# power_SCH1.net
KiCad netlist of a schematic drawn in Altium Designer
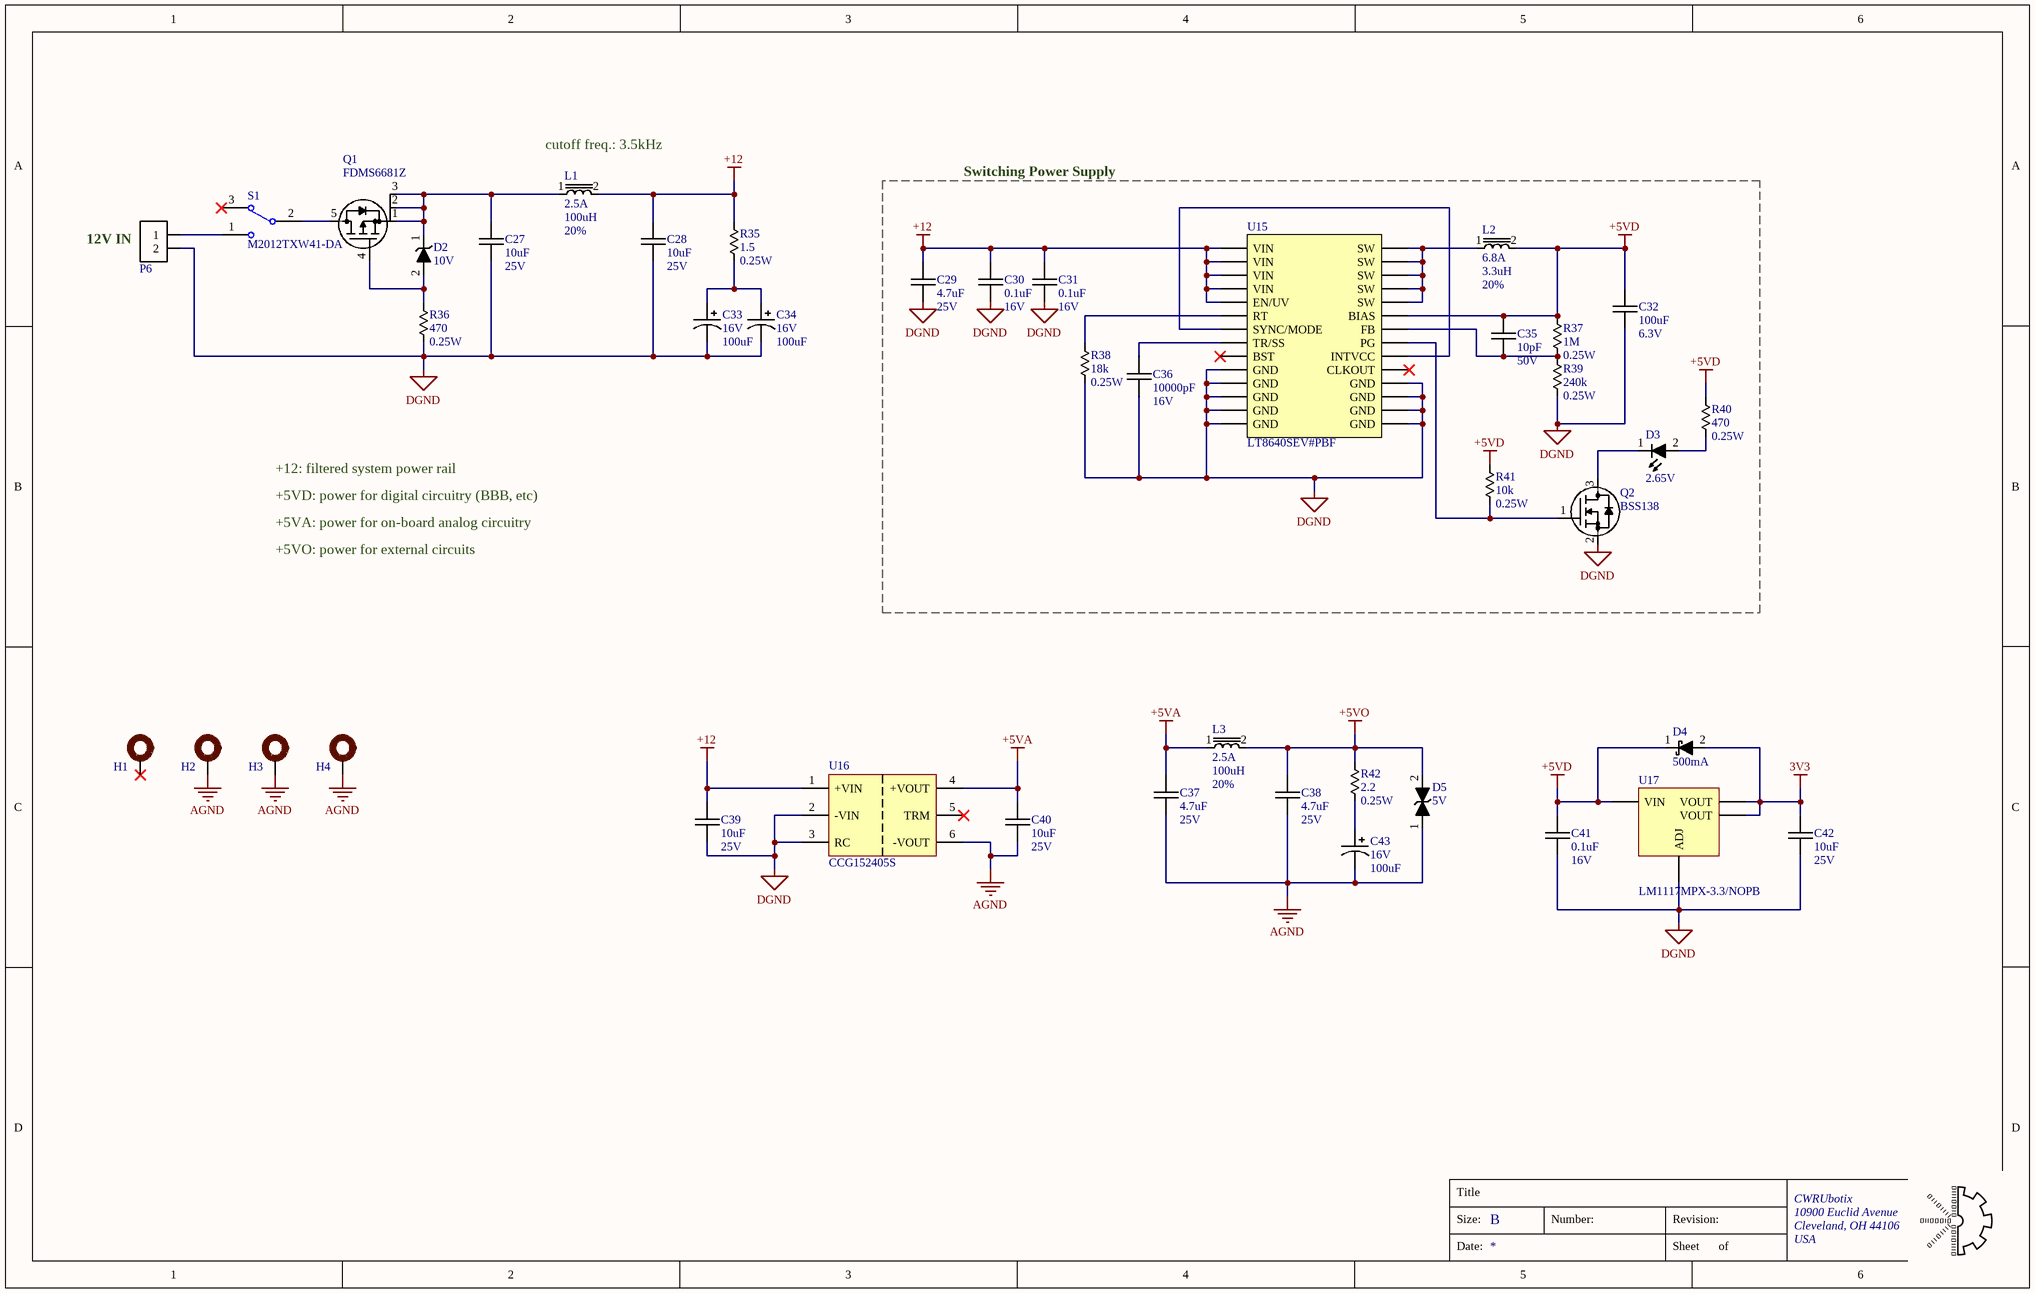
[diagram p0: power_SCH1.SchDoc]

(export (version "E")
  (design (tool "Eeschema 10.0.6"))
  (components
    (comp (ref "C27")
      (value "cap_single_np")
      (footprint "chip_1206")
      (description "CAP, 10uF, ±10%, 25V, X7R, 1206")
      (fields
        (field (name "TOLERANCE") "±10%")
        (field (name "CAPACITANCE") "10uF")
        (field (name "VOLTAGE RATING") "25V")
        (field (name "PART NUMBER") "CAP-00539")
      )
      (libsource (lib "Capacitors") (part "cap_single_np"))
    )
    (comp (ref "C28")
      (value "cap_single_np")
      (footprint "chip_1206")
      (description "CAP, 10uF, ±10%, 25V, X7R, 1206")
      (fields
        (field (name "TOLERANCE") "±10%")
        (field (name "CAPACITANCE") "10uF")
        (field (name "VOLTAGE RATING") "25V")
        (field (name "PART NUMBER") "CAP-00539")
      )
      (libsource (lib "Capacitors") (part "cap_single_np"))
    )
    (comp (ref "C29")
      (value "cap_single_np")
      (footprint "chip_0805")
      (description "CAP, 4.7uF, 10%, 25V, X7R, 0805")
      (fields
        (field (name "TOLERANCE") "10%")
        (field (name "CAPACITANCE") "4.7uF")
        (field (name "VOLTAGE RATING") "25V")
        (field (name "PART NUMBER") "CAP-00128")
      )
      (libsource (lib "Capacitors") (part "cap_single_np"))
    )
    (comp (ref "C30")
      (value "cap_single_np")
      (footprint "chip_0603")
      (description "CAP, 0.1uF, ±10%, 16V, X7R, 0603")
      (fields
        (field (name "TOLERANCE") "±10%")
        (field (name "CAPACITANCE") "0.1uF")
        (field (name "VOLTAGE RATING") "16V")
        (field (name "PART NUMBER") "CAP-00542")
      )
      (libsource (lib "Capacitors") (part "cap_single_np"))
    )
    (comp (ref "C31")
      (value "cap_single_np")
      (footprint "chip_0603")
      (description "CAP, 0.1uF, ±10%, 16V, X7R, 0603")
      (fields
        (field (name "TOLERANCE") "±10%")
        (field (name "CAPACITANCE") "0.1uF")
        (field (name "VOLTAGE RATING") "16V")
        (field (name "PART NUMBER") "CAP-00542")
      )
      (libsource (lib "Capacitors") (part "cap_single_np"))
    )
    (comp (ref "C32")
      (value "cap_single_np")
      (footprint "chip_1206")
      (description "CAP, 100uF, ±20%, 6.3V, X5R, 1206")
      (fields
        (field (name "TOLERANCE") "±20%")
        (field (name "CAPACITANCE") "100uF")
        (field (name "VOLTAGE RATING") "6.3V")
        (field (name "PART NUMBER") "CAP-00551")
      )
      (libsource (lib "Capacitors") (part "cap_single_np"))
    )
    (comp (ref "C33")
      (value "cap_single_p")
      (footprint "chip_2917_AVX_TAJD")
      (description "CAP, 100uF, ±10%, 16V, Tantalum, 2917")
      (fields
        (field (name "TOLERANCE") "±10%")
        (field (name "VOLTAGE RATING") "16V")
        (field (name "CAPACITANCE") "100uF")
        (field (name "PART NUMBER") "CAP-00550")
      )
      (libsource (lib "Capacitors") (part "cap_single_p"))
    )
    (comp (ref "C34")
      (value "cap_single_p")
      (footprint "chip_2917_AVX_TAJD")
      (description "CAP, 100uF, ±10%, 16V, Tantalum, 2917")
      (fields
        (field (name "TOLERANCE") "±10%")
        (field (name "VOLTAGE RATING") "16V")
        (field (name "CAPACITANCE") "100uF")
        (field (name "PART NUMBER") "CAP-00550")
      )
      (libsource (lib "Capacitors") (part "cap_single_p"))
    )
    (comp (ref "C35")
      (value "cap_single_np")
      (footprint "chip_0603")
      (description "CAP, 10pF, ±2%, 50V, C0G, 0603")
      (fields
        (field (name "TOLERANCE") "±2%")
        (field (name "CAPACITANCE") "10pF")
        (field (name "VOLTAGE RATING") "50V")
        (field (name "PART NUMBER") "CAP-00471")
      )
      (libsource (lib "Capacitors") (part "cap_single_np"))
    )
    (comp (ref "C36")
      (value "cap_single_np")
      (footprint "chip_0603")
      (description "CAP, 10000pF, ±10%, 16V, X7R, 0603")
      (fields
        (field (name "TOLERANCE") "±10%")
        (field (name "CAPACITANCE") "10000pF")
        (field (name "VOLTAGE RATING") "16V")
        (field (name "PART NUMBER") "CAP-00543")
      )
      (libsource (lib "Capacitors") (part "cap_single_np"))
    )
    (comp (ref "C37")
      (value "cap_single_np")
      (footprint "chip_0805")
      (description "CAP, 4.7uF, 10%, 25V, X7R, 0805")
      (fields
        (field (name "TOLERANCE") "10%")
        (field (name "CAPACITANCE") "4.7uF")
        (field (name "VOLTAGE RATING") "25V")
        (field (name "PART NUMBER") "CAP-00128")
      )
      (libsource (lib "Capacitors") (part "cap_single_np"))
    )
    (comp (ref "C38")
      (value "cap_single_np")
      (footprint "chip_0805")
      (description "CAP, 4.7uF, 10%, 25V, X7R, 0805")
      (fields
        (field (name "TOLERANCE") "10%")
        (field (name "CAPACITANCE") "4.7uF")
        (field (name "VOLTAGE RATING") "25V")
        (field (name "PART NUMBER") "CAP-00128")
      )
      (libsource (lib "Capacitors") (part "cap_single_np"))
    )
    (comp (ref "C39")
      (value "cap_single_np")
      (footprint "chip_1206")
      (description "CAP, 10uF, ±10%, 25V, X7R, 1206")
      (fields
        (field (name "TOLERANCE") "±10%")
        (field (name "CAPACITANCE") "10uF")
        (field (name "VOLTAGE RATING") "25V")
        (field (name "PART NUMBER") "CAP-00539")
      )
      (libsource (lib "Capacitors") (part "cap_single_np"))
    )
    (comp (ref "C40")
      (value "cap_single_np")
      (footprint "chip_1206")
      (description "CAP, 10uF, ±10%, 25V, X7R, 1206")
      (fields
        (field (name "TOLERANCE") "±10%")
        (field (name "CAPACITANCE") "10uF")
        (field (name "VOLTAGE RATING") "25V")
        (field (name "PART NUMBER") "CAP-00539")
      )
      (libsource (lib "Capacitors") (part "cap_single_np"))
    )
    (comp (ref "C41")
      (value "cap_single_np")
      (footprint "chip_0603")
      (description "CAP, 0.1uF, ±10%, 16V, X7R, 0603")
      (fields
        (field (name "TOLERANCE") "±10%")
        (field (name "CAPACITANCE") "0.1uF")
        (field (name "VOLTAGE RATING") "16V")
        (field (name "PART NUMBER") "CAP-00542")
      )
      (libsource (lib "Capacitors") (part "cap_single_np"))
    )
    (comp (ref "C42")
      (value "cap_single_np")
      (footprint "chip_1206")
      (description "CAP, 10uF, ±10%, 25V, X7R, 1206")
      (fields
        (field (name "TOLERANCE") "±10%")
        (field (name "CAPACITANCE") "10uF")
        (field (name "VOLTAGE RATING") "25V")
        (field (name "PART NUMBER") "CAP-00539")
      )
      (libsource (lib "Capacitors") (part "cap_single_np"))
    )
    (comp (ref "C43")
      (value "cap_single_p")
      (footprint "chip_2917_AVX_TAJD")
      (description "CAP, 100uF, ±10%, 16V, Tantalum, 2917")
      (fields
        (field (name "TOLERANCE") "±10%")
        (field (name "VOLTAGE RATING") "16V")
        (field (name "CAPACITANCE") "100uF")
        (field (name "PART NUMBER") "CAP-00550")
      )
      (libsource (lib "Capacitors") (part "cap_single_p"))
    )
    (comp (ref "D2")
      (value "diode_1")
      (footprint "sod323_0")
      (description "Dio Zen, 10V, 2%, 200mW, SOD-323")
      (fields
        (field (name "REVERSE BREAKDOWN VOLTAGE") "10V")
        (field (name "PART NUMBER") "DIO-00019")
        (field (name "TOLERANCE") "2%")
      )
      (libsource (lib "Diodes") (part "diode_1"))
    )
    (comp (ref "D3")
      (value "diode_4")
      (footprint "chip_0603")
      (description "LED, Blue, 0603, Low current, HELI2 Series")
      (fields
        (field (name "FORWARD VOLTAGE") "2.65V")
        (field (name "PART NUMBER") "DIO-00049")
        (field (name "MANUFACTURER") "Kingbright")
      )
      (libsource (lib "Diodes") (part "diode_4"))
    )
    (comp (ref "D4")
      (value "diode_2")
      (footprint "sod323_0")
      (description "Dio Shtky, 500mA, 0.62V, 30V, SOD-323")
      (fields
        (field (name "CURRENT RATING") "500mA")
        (field (name "PART NUMBER") "DIO-00000")
        (field (name "MANUFACTURER") "ON Semi")
      )
      (libsource (lib "Diodes") (part "diode_2"))
    )
    (comp (ref "D5")
      (value "diode_5")
      (footprint "do-214ac")
      (description "TVS, 5V, 400W")
      (fields
        (field (name "REVERSE BREAKDOWN VOLTAGE") "5V")
        (field (name "PART NUMBER") "DIO-00036")
        (field (name "MANUFACTURER") "ST")
      )
      (libsource (lib "Diodes") (part "diode_5"))
    )
    (comp (ref "H1")
      (value "mounting_hole_0")
      (footprint "#8-32_SOCKET_HEAD")
      (description "#8-32 Mounting Hole for Socket Head Cap Screw")
      (fields (field (name "PART NUMBER") "MISC-00027"))
      (libsource (lib "Misc") (part "mounting_hole_0"))
    )
    (comp (ref "H2")
      (value "mounting_hole_0")
      (footprint "#8-32_SOCKET_HEAD")
      (description "#8-32 Mounting Hole for Socket Head Cap Screw")
      (fields (field (name "PART NUMBER") "MISC-00027"))
      (libsource (lib "Misc") (part "mounting_hole_0"))
    )
    (comp (ref "H3")
      (value "mounting_hole_0")
      (footprint "#8-32_SOCKET_HEAD")
      (description "#8-32 Mounting Hole for Socket Head Cap Screw")
      (fields (field (name "PART NUMBER") "MISC-00027"))
      (libsource (lib "Misc") (part "mounting_hole_0"))
    )
    (comp (ref "H4")
      (value "mounting_hole_0")
      (footprint "#8-32_SOCKET_HEAD")
      (description "#8-32 Mounting Hole for Socket Head Cap Screw")
      (fields (field (name "PART NUMBER") "MISC-00027"))
      (libsource (lib "Misc") (part "mounting_hole_0"))
    )
    (comp (ref "L1")
      (value "ind_1")
      (footprint "WURTH_7447709101")
      (description "Ind, 100uH, 20%, 2.5A, 0.11 Ohm")
      (fields
        (field (name "CURRENT RATING") "2.5A")
        (field (name "INDUCTANCE") "100uH")
        (field (name "TOLERANCE") "20%")
        (field (name "PART NUMBER") "MAG-00102")
        (field (name "MANUFACTURER") "Wurth")
      )
      (libsource (lib "Magnetics") (part "ind_1"))
    )
    (comp (ref "L2")
      (value "ind_1")
      (footprint "TDK_SPM6530")
      (description "Ind, 3.3uH, 20%, 6.8A, EP5")
      (fields
        (field (name "CURRENT RATING") "6.8A")
        (field (name "INDUCTANCE") "3.3uH")
        (field (name "TOLERANCE") "20%")
        (field (name "PART NUMBER") "MAG-00093")
        (field (name "MANUFACTURER") "TDK")
      )
      (libsource (lib "Magnetics") (part "ind_1"))
    )
    (comp (ref "L3")
      (value "ind_1")
      (footprint "WURTH_7447709101")
      (description "Ind, 100uH, 20%, 2.5A, 0.11 Ohm")
      (fields
        (field (name "CURRENT RATING") "2.5A")
        (field (name "INDUCTANCE") "100uH")
        (field (name "TOLERANCE") "20%")
        (field (name "PART NUMBER") "MAG-00102")
        (field (name "MANUFACTURER") "Wurth")
      )
      (libsource (lib "Magnetics") (part "ind_1"))
    )
    (comp (ref "P6")
      (value "conn-2x1_0")
      (footprint "TERM_3.50MM_2x1_0")
      (description "Term Blk, 2 Pos, 16A, 3.5mm Pitch")
      (fields (field (name "PART NUMBER") "CONN-00023") (field (name "MANUFACTURER") "Phoenix Contact"))
      (libsource (lib "Connectors") (part "conn-2x1_0"))
    )
    (comp (ref "Q1")
      (value "p-mosfet_3")
      (footprint "PQFN-8-5x6")
      (description "XSTR PMOS, 21.1A, 30V, Vgs 3V, PQFN8 5X6")
      (fields
        (field (name "MANUFACTURER PN") "FDMS6681Z")
        (field (name "PART NUMBER") "XSTR-00026")
        (field (name "MANUFACTURER") "ON Semi")
      )
      (libsource (lib "Transistors") (part "p-mosfet_3"))
    )
    (comp (ref "Q2")
      (value "n-mosfet_1")
      (footprint "sot-23-3")
      (description "XSTR NMOS, 220mA, 50V, Vgs 1.3V, SOT-23-3")
      (fields
        (field (name "MANUFACTURER PN") "BSS138")
        (field (name "PART NUMBER") "XSTR-00017")
        (field (name "MANUFACTURER") "ON Semi")
      )
      (libsource (lib "Transistors") (part "n-mosfet_1"))
    )
    (comp (ref "R35")
      (value "res_single")
      (footprint "chip_0805")
      (description "RES SMD 1.5 OHM 1% 1/4W 0805")
      (fields
        (field (name "TOLERANCE") "1%")
        (field (name "RESISTANCE") "1.5")
        (field (name "POWER RATING") "0.25W")
        (field (name "PART NUMBER") "RES-00600")
      )
      (libsource (lib "Resistors") (part "res_single"))
    )
    (comp (ref "R36")
      (value "res_single")
      (footprint "chip_0603")
      (description "RES SMD 470 OHM 1% 1/4W 0603")
      (fields
        (field (name "TOLERANCE") "1%")
        (field (name "RESISTANCE") "470")
        (field (name "POWER RATING") "0.25W")
        (field (name "PART NUMBER") "RES-00236")
      )
      (libsource (lib "Resistors") (part "res_single"))
    )
    (comp (ref "R37")
      (value "res_single")
      (footprint "chip_0603")
      (description "RES SMD 1M OHM 1% 1/4W 0603")
      (fields
        (field (name "TOLERANCE") "1%")
        (field (name "RESISTANCE") "1M")
        (field (name "POWER RATING") "0.25W")
        (field (name "PART NUMBER") "RES-00362")
      )
      (libsource (lib "Resistors") (part "res_single"))
    )
    (comp (ref "R38")
      (value "res_single")
      (footprint "chip_0603")
      (description "RES SMD 18K OHM 1% 1/4W 0603")
      (fields
        (field (name "TOLERANCE") "1%")
        (field (name "RESISTANCE") "18k")
        (field (name "POWER RATING") "0.25W")
        (field (name "PART NUMBER") "RES-00356")
      )
      (libsource (lib "Resistors") (part "res_single"))
    )
    (comp (ref "R39")
      (value "res_single")
      (footprint "chip_0603")
      (description "RES SMD 240K OHM 1% 1/4W 0603")
      (fields
        (field (name "TOLERANCE") "1%")
        (field (name "RESISTANCE") "240k")
        (field (name "POWER RATING") "0.25W")
        (field (name "PART NUMBER") "RES-00397")
      )
      (libsource (lib "Resistors") (part "res_single"))
    )
    (comp (ref "R40")
      (value "res_single")
      (footprint "chip_0603")
      (description "RES SMD 470 OHM 1% 1/4W 0603")
      (fields
        (field (name "TOLERANCE") "1%")
        (field (name "RESISTANCE") "470")
        (field (name "POWER RATING") "0.25W")
        (field (name "PART NUMBER") "RES-00236")
      )
      (libsource (lib "Resistors") (part "res_single"))
    )
    (comp (ref "R41")
      (value "res_single")
      (footprint "chip_0603")
      (description "RES SMD 10K OHM 1% 1/4W 0603")
      (fields
        (field (name "TOLERANCE") "1%")
        (field (name "RESISTANCE") "10k")
        (field (name "POWER RATING") "0.25W")
        (field (name "PART NUMBER") "RES-00306")
      )
      (libsource (lib "Resistors") (part "res_single"))
    )
    (comp (ref "R42")
      (value "res_single")
      (footprint "chip_0805")
      (description "RES SMD 2.2 OHM 1% 1/4W 0805")
      (fields
        (field (name "TOLERANCE") "1%")
        (field (name "RESISTANCE") "2.2")
        (field (name "POWER RATING") "0.25W")
        (field (name "PART NUMBER") "RES-00601")
      )
      (libsource (lib "Resistors") (part "res_single"))
    )
    (comp (ref "S1")
      (value "SW-SPDT")
      (footprint "M2012TXG41-DC")
      (description "Switch, SPDT, Rocker, Thru-hole, Right-angle")
      (fields
        (field (name "MANUFACTURER PN") "M2012TXW41-DA")
        (field (name "PART NUMBER") "MISC-00009")
        (field (name "MANUFACTURER") "NKK Switches")
      )
      (libsource (lib "Misc") (part "SW-SPDT"))
    )
    (comp (ref "U15")
      (value "LT8640S")
      (footprint "LQFN-24_0")
      (description "SW Reg, Silent Switcher 2, Low EMI")
      (fields
        (field (name "MANUFACTURER PN") "LT8640SEV#PBF")
        (field (name "PART NUMBER") "PWREG-00013")
        (field (name "MANUFACTURER") "Analog Devices")
      )
      (libsource (lib "Power Reg") (part "LT8640S"))
    )
    (comp (ref "U16")
      (value "CCG15")
      (footprint "CCG15")
      (description "Module, Isolated, 5V, 3A")
      (fields
        (field (name "MANUFACTURER PN") "CCG152405S")
        (field (name "PART NUMBER") "PWREG-00021")
        (field (name "MANUFACTURER") "TDK-Lambda")
      )
      (libsource (lib "Power Reg") (part "CCG15"))
    )
    (comp (ref "U17")
      (value "LM1117")
      (footprint "sot-223-4")
      (description "REG, Linear, Fixed 3V3, 800mA, SOT-223")
      (fields
        (field (name "MANUFACTURER PN") "LM1117MPX-3.3/NOPB")
        (field (name "PART NUMBER") "PWREG-00018")
        (field (name "MANUFACTURER") "TI")
      )
      (libsource (lib "Power Reg") (part "LM1117"))
    )
  )
  (nets
    (net (code "1") (name "+5VA") (class "Default")
      (node (ref "C37") (pin "1") (pinfunction "1_1") (pintype "passive"))
      (node (ref "C40") (pin "1") (pinfunction "1_1") (pintype "passive"))
      (node (ref "L3") (pin "1") (pinfunction "1_1") (pintype "passive"))
      (node (ref "U16") (pin "4") (pinfunction "+VOUT_4") (pintype "power_in"))
    )
    (net (code "2") (name "+5VD") (class "Default")
      (node (ref "C32") (pin "1") (pinfunction "1_1") (pintype "passive"))
      (node (ref "C35") (pin "1") (pinfunction "1_1") (pintype "passive"))
      (node (ref "C41") (pin "1") (pinfunction "1_1") (pintype "passive"))
      (node (ref "D4") (pin "1") (pinfunction "1_1") (pintype "passive"))
      (node (ref "L2") (pin "2") (pinfunction "2_2") (pintype "passive"))
      (node (ref "R37") (pin "1") (pinfunction "1_1") (pintype "passive"))
      (node (ref "R40") (pin "2") (pinfunction "2_2") (pintype "passive"))
      (node (ref "R41") (pin "1") (pinfunction "1_1") (pintype "passive"))
      (node (ref "U15") (pin "1") (pinfunction "BIAS_1") (pintype "passive"))
      (node (ref "U17") (pin "3") (pinfunction "VIN_3") (pintype "passive"))
    )
    (net (code "3") (name "+5VO") (class "Default")
      (node (ref "C38") (pin "1") (pinfunction "1_1") (pintype "passive"))
      (node (ref "D5") (pin "2") (pinfunction "2_2") (pintype "passive"))
      (node (ref "L3") (pin "2") (pinfunction "2_2") (pintype "passive"))
      (node (ref "R42") (pin "1") (pinfunction "1_1") (pintype "passive"))
    )
    (net (code "4") (name "+12") (class "Default")
      (node (ref "C28") (pin "1") (pinfunction "1_1") (pintype "passive"))
      (node (ref "C29") (pin "1") (pinfunction "1_1") (pintype "passive"))
      (node (ref "C30") (pin "1") (pinfunction "1_1") (pintype "passive"))
      (node (ref "C31") (pin "1") (pinfunction "1_1") (pintype "passive"))
      (node (ref "C39") (pin "1") (pinfunction "1_1") (pintype "passive"))
      (node (ref "L1") (pin "2") (pinfunction "2_2") (pintype "passive"))
      (node (ref "R35") (pin "1") (pinfunction "1_1") (pintype "passive"))
      (node (ref "U15") (pin "13") (pinfunction "VIN_13") (pintype "passive"))
      (node (ref "U15") (pin "14") (pinfunction "VIN_14") (pintype "passive"))
      (node (ref "U15") (pin "17") (pinfunction "EN/UV_17") (pintype "passive"))
      (node (ref "U15") (pin "5") (pinfunction "VIN_5") (pintype "passive"))
      (node (ref "U15") (pin "6") (pinfunction "VIN_6") (pintype "passive"))
      (node (ref "U16") (pin "1") (pinfunction "+VIN_1") (pintype "passive"))
    )
    (net (code "5") (name "3V3") (class "Default")
      (node (ref "C42") (pin "1") (pinfunction "1_1") (pintype "passive"))
      (node (ref "D4") (pin "2") (pinfunction "2_2") (pintype "passive"))
      (node (ref "U17") (pin "2") (pinfunction "VOUT_2") (pintype "passive"))
      (node (ref "U17") (pin "4") (pinfunction "VOUT_4") (pintype "passive"))
    )
    (net (code "6") (name "AGND") (class "Default")
      (node (ref "C37") (pin "2") (pinfunction "2_2") (pintype "passive"))
      (node (ref "C38") (pin "2") (pinfunction "2_2") (pintype "passive"))
      (node (ref "C40") (pin "2") (pinfunction "2_2") (pintype "passive"))
      (node (ref "C43") (pin "2") (pinfunction "2_2") (pintype "passive"))
      (node (ref "D5") (pin "1") (pinfunction "1_1") (pintype "passive"))
      (node (ref "H2") (pin "0") (pinfunction "A_0") (pintype "passive"))
      (node (ref "H3") (pin "0") (pinfunction "A_0") (pintype "passive"))
      (node (ref "H4") (pin "0") (pinfunction "A_0") (pintype "passive"))
      (node (ref "U16") (pin "6") (pinfunction "-VOUT_6") (pintype "power_in"))
    )
    (net (code "7") (name "DGND") (class "Default")
      (node (ref "C27") (pin "2") (pinfunction "2_2") (pintype "passive"))
      (node (ref "C28") (pin "2") (pinfunction "2_2") (pintype "passive"))
      (node (ref "C29") (pin "2") (pinfunction "2_2") (pintype "passive"))
      (node (ref "C30") (pin "2") (pinfunction "2_2") (pintype "passive"))
      (node (ref "C31") (pin "2") (pinfunction "2_2") (pintype "passive"))
      (node (ref "C32") (pin "2") (pinfunction "2_2") (pintype "passive"))
      (node (ref "C33") (pin "2") (pinfunction "2_2") (pintype "passive"))
      (node (ref "C34") (pin "2") (pinfunction "2_2") (pintype "passive"))
      (node (ref "C36") (pin "2") (pinfunction "2_2") (pintype "passive"))
      (node (ref "C39") (pin "2") (pinfunction "2_2") (pintype "passive"))
      (node (ref "C41") (pin "2") (pinfunction "2_2") (pintype "passive"))
      (node (ref "C42") (pin "2") (pinfunction "2_2") (pintype "passive"))
      (node (ref "P6") (pin "2") (pinfunction "2_2") (pintype "passive"))
      (node (ref "Q2") (pin "2") (pinfunction "S_2") (pintype "passive"))
      (node (ref "R36") (pin "2") (pinfunction "2_2") (pintype "passive"))
      (node (ref "R38") (pin "2") (pinfunction "2_2") (pintype "passive"))
      (node (ref "R39") (pin "2") (pinfunction "2_2") (pintype "passive"))
      (node (ref "U15") (pin "15") (pinfunction "GND_15") (pintype "passive"))
      (node (ref "U15") (pin "16") (pinfunction "GND_16") (pintype "passive"))
      (node (ref "U15") (pin "25") (pinfunction "GND_25") (pintype "passive"))
      (node (ref "U15") (pin "26") (pinfunction "GND_26") (pintype "passive"))
      (node (ref "U15") (pin "27") (pinfunction "GND_27") (pintype "passive"))
      (node (ref "U15") (pin "28") (pinfunction "GND_28") (pintype "passive"))
      (node (ref "U15") (pin "3") (pinfunction "GND_3") (pintype "passive"))
      (node (ref "U15") (pin "4") (pinfunction "GND_4") (pintype "passive"))
      (node (ref "U16") (pin "2") (pinfunction "-VIN_2") (pintype "passive"))
      (node (ref "U16") (pin "3") (pinfunction "RC_3") (pintype "passive"))
      (node (ref "U17") (pin "1") (pinfunction "ADJ_1") (pintype "passive"))
    )
    (net (code "8") (name "Net-(C27-Pad1)") (class "Default")
      (node (ref "C27") (pin "1") (pinfunction "1_1") (pintype "passive"))
      (node (ref "D2") (pin "1") (pinfunction "1_1") (pintype "passive"))
      (node (ref "L1") (pin "1") (pinfunction "1_1") (pintype "passive"))
      (node (ref "Q1") (pin "1") (pinfunction "S_1") (pintype "passive"))
      (node (ref "Q1") (pin "2") (pinfunction "S_2") (pintype "passive"))
      (node (ref "Q1") (pin "3") (pinfunction "S_3") (pintype "passive"))
    )
    (net (code "9") (name "Net-(C33-Pad1)") (class "Default")
      (node (ref "C33") (pin "1") (pinfunction "1_1") (pintype "passive"))
      (node (ref "C34") (pin "1") (pinfunction "1_1") (pintype "passive"))
      (node (ref "R35") (pin "2") (pinfunction "2_2") (pintype "passive"))
    )
    (net (code "10") (name "Net-(C43-Pad1)") (class "Default")
      (node (ref "C43") (pin "1") (pinfunction "1_1") (pintype "passive"))
      (node (ref "R42") (pin "2") (pinfunction "2_2") (pintype "passive"))
    )
    (net (code "11") (name "Net-(D3-Pad2)") (class "Default")
      (node (ref "D3") (pin "2") (pinfunction "2_2") (pintype "passive"))
      (node (ref "R40") (pin "1") (pinfunction "1_1") (pintype "passive"))
    )
    (net (code "12") (name "Net-(L2-Pad1)") (class "Default")
      (node (ref "L2") (pin "1") (pinfunction "1_1") (pintype "passive"))
      (node (ref "U15") (pin "10") (pinfunction "SW_10") (pintype "passive"))
      (node (ref "U15") (pin "11") (pinfunction "SW_11") (pintype "passive"))
      (node (ref "U15") (pin "12") (pinfunction "SW_12") (pintype "passive"))
      (node (ref "U15") (pin "8") (pinfunction "SW_8") (pintype "passive"))
      (node (ref "U15") (pin "9") (pinfunction "SW_9") (pintype "passive"))
    )
    (net (code "13") (name "Net-(P6-Pad1)") (class "Default")
      (node (ref "P6") (pin "1") (pinfunction "1_1") (pintype "passive"))
      (node (ref "S1") (pin "1") (pinfunction "1_1") (pintype "passive"))
    )
    (net (code "14") (name "Net-(Q1-D)") (class "Default")
      (node (ref "Q1") (pin "5") (pinfunction "D_5") (pintype "passive"))
      (node (ref "S1") (pin "2") (pinfunction "2_2") (pintype "passive"))
    )
    (net (code "15") (name "Net-(Q1-G)") (class "Default")
      (node (ref "D2") (pin "2") (pinfunction "2_2") (pintype "passive"))
      (node (ref "Q1") (pin "4") (pinfunction "G_4") (pintype "passive"))
      (node (ref "R36") (pin "1") (pinfunction "1_1") (pintype "passive"))
    )
    (net (code "16") (name "Net-(Q2-D)") (class "Default")
      (node (ref "D3") (pin "1") (pinfunction "1_1") (pintype "passive"))
      (node (ref "Q2") (pin "3") (pinfunction "D_3") (pintype "passive"))
    )
    (net (code "17") (name "Net-(Q2-G)") (class "Default")
      (node (ref "Q2") (pin "1") (pinfunction "G_1") (pintype "passive"))
      (node (ref "R41") (pin "2") (pinfunction "2_2") (pintype "passive"))
      (node (ref "U15") (pin "23") (pinfunction "PG_23") (pintype "passive"))
    )
    (net (code "18") (name "Net-(U15-FB)") (class "Default")
      (node (ref "C35") (pin "2") (pinfunction "2_2") (pintype "passive"))
      (node (ref "R37") (pin "2") (pinfunction "2_2") (pintype "passive"))
      (node (ref "R39") (pin "1") (pinfunction "1_1") (pintype "passive"))
      (node (ref "U15") (pin "24") (pinfunction "FB_24") (pintype "passive"))
    )
    (net (code "19") (name "Net-(U15-INTVCC)") (class "Default")
      (node (ref "U15") (pin "2") (pinfunction "INTVCC_2") (pintype "passive"))
      (node (ref "U15") (pin "20") (pinfunction "SYNC/MODE_20") (pintype "passive"))
    )
    (net (code "20") (name "Net-(U15-RT)") (class "Default")
      (node (ref "R38") (pin "1") (pinfunction "1_1") (pintype "passive"))
      (node (ref "U15") (pin "18") (pinfunction "RT_18") (pintype "passive"))
    )
    (net (code "21") (name "Net-(U15-TR{slash}SS)") (class "Default")
      (node (ref "C36") (pin "1") (pinfunction "1_1") (pintype "passive"))
      (node (ref "U15") (pin "21") (pinfunction "TR/SS_21") (pintype "passive"))
    )
    (net (code "22") (name "unconnected-(H1-A-Pad0)") (class "Default")
      (node (ref "H1") (pin "0") (pinfunction "A_0") (pintype "passive+no_connect"))
    )
    (net (code "23") (name "unconnected-(S1-Pad3)") (class "Default")
      (node (ref "S1") (pin "3") (pinfunction "3_3") (pintype "passive+no_connect"))
    )
    (net (code "24") (name "unconnected-(U15-BST-Pad7)") (class "Default")
      (node (ref "U15") (pin "7") (pinfunction "BST_7") (pintype "passive+no_connect"))
    )
    (net (code "25") (name "unconnected-(U15-CLKOUT-Pad19)") (class "Default")
      (node (ref "U15") (pin "19") (pinfunction "CLKOUT_19") (pintype "passive+no_connect"))
    )
    (net (code "26") (name "unconnected-(U16-TRM-Pad5)") (class "Default")
      (node (ref "U16") (pin "5") (pinfunction "TRM_5") (pintype "passive+no_connect"))
    )
  )
)
